# bluetooth_version.net
KiCad netlist of a schematic drawn in EAGLE
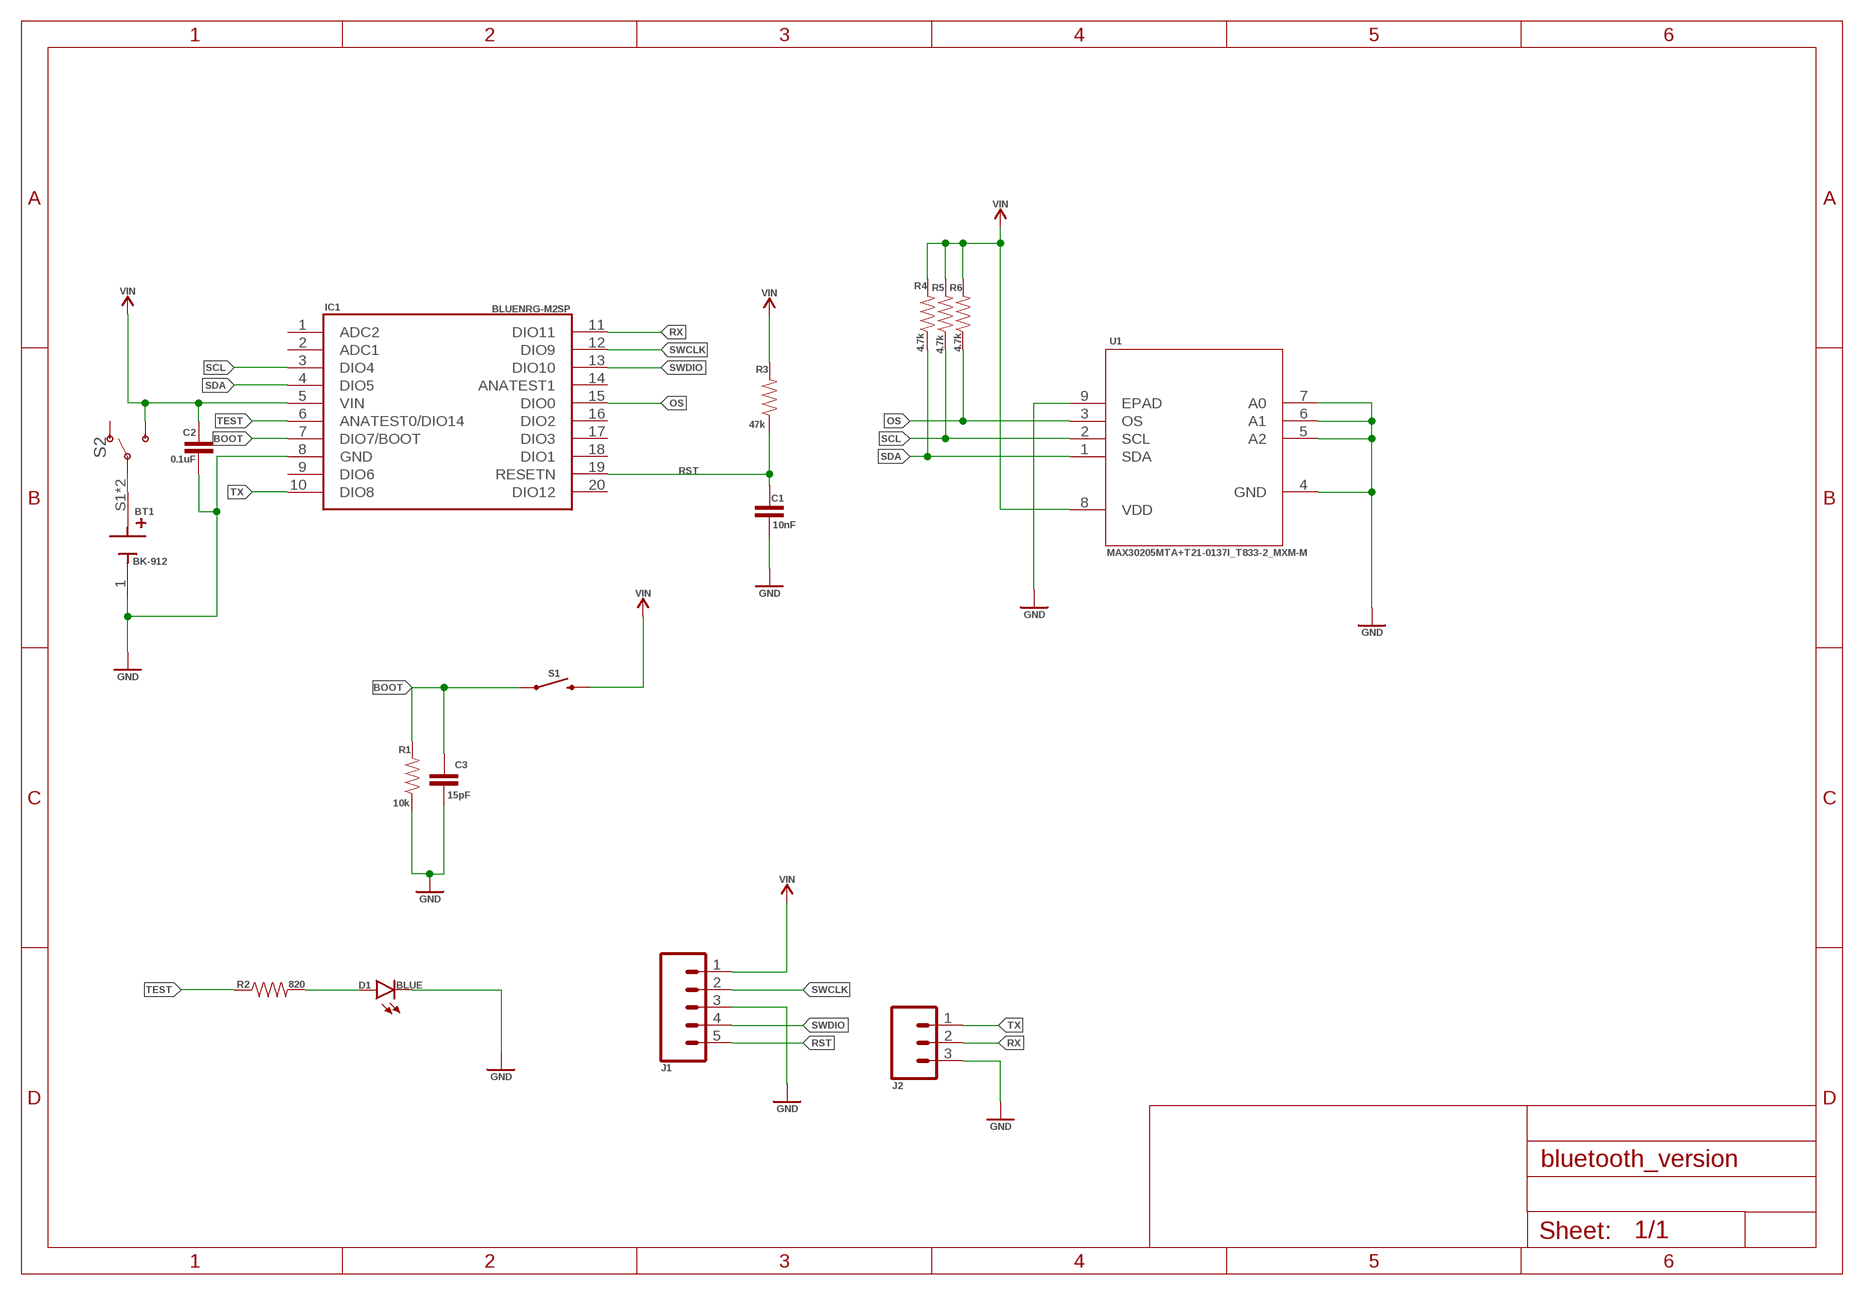
[diagram p0: schematic, sheet 1]

(export (version "E")
  (design (tool "Eeschema 10.0.6"))
  (components
    (comp (ref "BT1")
      (value "BK-912")
      (footprint "eagle-import:BAT_BK-912")
      (fields (field (name "MF") "MPD (Memory"))
      (libsource (lib "eagle-import") (part "BK-912"))
    )
    (comp (ref "C1")
      (value "10nF")
      (footprint "eagle-import:0603")
      (libsource (lib "eagle-import") (part "10NF-0603-50V-10%"))
    )
    (comp (ref "C2")
      (value "0.1uF")
      (footprint "eagle-import:0603")
      (libsource (lib "eagle-import") (part "0.1UF-0603-25V-(+80/-20%)"))
    )
    (comp (ref "C3")
      (value "15pF")
      (footprint "eagle-import:0603")
      (libsource (lib "eagle-import") (part "15PF-0603-50V-5%"))
    )
    (comp (ref "D1")
      (value "BLUE")
      (footprint "eagle-import:LED-0603")
      (libsource (lib "eagle-import") (part "LED-BLUE0603"))
    )
    (comp (ref "IC1")
      (value "BLUENRG-M2SP")
      (footprint "eagle-import:BLUENRGM2SP")
      (fields (field (name "MOUSER_PART_NUMBER") "511-BLUENRG-M2SP"))
      (libsource (lib "eagle-import") (part "BLUENRG-M2SP"))
    )
    (comp (ref "J1")
      (value "CONN_05")
      (footprint "eagle-import:1X05")
      (libsource (lib "eagle-import") (part "CONN_05"))
    )
    (comp (ref "J2")
      (value "455-1750-1-ND")
      (footprint "eagle-import:1X03")
      (libsource (lib "eagle-import") (part "CONN_03"))
    )
    (comp (ref "R1")
      (value "10k")
      (footprint "eagle-import:0603")
      (libsource (lib "eagle-import") (part "10KOHM-0603-1/10W-1%"))
    )
    (comp (ref "R2")
      (value "820")
      (footprint "eagle-import:0603")
      (fields (field (name "SPICEPREFIX") "R"))
      (libsource (lib "eagle-import") (part "8.2KOHM-0603-1/10W-5%"))
    )
    (comp (ref "R3")
      (value "47k")
      (footprint "eagle-import:0603")
      (libsource (lib "eagle-import") (part "47KOHM-0603-1/10W-1%"))
    )
    (comp (ref "R4")
      (value "4.7k")
      (footprint "eagle-import:0603")
      (libsource (lib "eagle-import") (part "4.7KOHM-0603-1/10W-1%"))
    )
    (comp (ref "R5")
      (value "4.7k")
      (footprint "eagle-import:0603")
      (libsource (lib "eagle-import") (part "4.7KOHM-0603-1/10W-1%"))
    )
    (comp (ref "R6")
      (value "4.7k")
      (footprint "eagle-import:0603")
      (libsource (lib "eagle-import") (part "4.7KOHM-0603-1/10W-1%"))
    )
    (comp (ref "S1")
      (value "MOMENTARY-SWITCH-SPST-SMD-4.6X2.8MM")
      (footprint "eagle-import:TACTILE_SWITCH_SMD_4.6X2.8MM")
      (libsource (lib "eagle-import") (part "MOMENTARY-SWITCH-SPST-SMD-4.6X2.8MM"))
    )
    (comp (ref "S2")
      (value "SWITCH-SPDT-SMD-RIGHT-ANGLE")
      (footprint "eagle-import:SWITCH_SPST_SMD_A")
      (libsource (lib "eagle-import") (part "SWITCH-SPDT-SMD-RIGHT-ANGLE"))
    )
    (comp (ref "U1")
      (value "MAX30205MTA+T21-0137I_T833-2_MXM-M")
      (footprint "eagle-import:21-0137I_T833-2_MXM-M")
      (fields
        (field (name "MANUFACTURER_PART_NUMBER") "MAX30205MTA+T")
        (field (name "COPYRIGHT") "Copyright (C) 2018 Accelerated Designs. All rights reserved")
      )
      (libsource (lib "eagle-import") (part "MAX30205MTA+T21-0137I_T833-2_MXM-M"))
    )
  )
  (nets
    (net (code "1") (name "BOOT") (class "Default")
      (node (ref "C3") (pin "1") (pinfunction "1_1") (pintype "passive"))
      (node (ref "IC1") (pin "7") (pinfunction "DIO7/BOOT_7") (pintype "bidirectional"))
      (node (ref "R1") (pin "2") (pinfunction "2_2") (pintype "passive"))
      (node (ref "S1") (pin "1") (pinfunction "1_1") (pintype "passive"))
      (node (ref "S1") (pin "2") (pinfunction "1_2") (pintype "passive"))
    )
    (net (code "2") (name "GND") (class "Default")
      (node (ref "BT1") (pin "1") (pinfunction "-_1") (pintype "passive"))
      (node (ref "C1") (pin "2") (pinfunction "2_2") (pintype "passive"))
      (node (ref "C2") (pin "2") (pinfunction "2_2") (pintype "passive"))
      (node (ref "C3") (pin "2") (pinfunction "2_2") (pintype "passive"))
      (node (ref "D1") (pin "C") (pinfunction "C_C") (pintype "passive"))
      (node (ref "IC1") (pin "8") (pinfunction "GND_8") (pintype "bidirectional"))
      (node (ref "J1") (pin "3") (pinfunction "3_3") (pintype "passive"))
      (node (ref "J2") (pin "3") (pinfunction "3_3") (pintype "passive"))
      (node (ref "R1") (pin "1") (pinfunction "1_1") (pintype "passive"))
      (node (ref "U1") (pin "4") (pinfunction "GND_4") (pintype "passive"))
      (node (ref "U1") (pin "5") (pinfunction "A2_5") (pintype "bidirectional"))
      (node (ref "U1") (pin "6") (pinfunction "A1_6") (pintype "bidirectional"))
      (node (ref "U1") (pin "7") (pinfunction "A0_7") (pintype "bidirectional"))
      (node (ref "U1") (pin "9") (pinfunction "EPAD_9") (pintype "passive"))
    )
    (net (code "3") (name "Net-(D1-PadA)") (class "Default")
      (node (ref "D1") (pin "A") (pinfunction "A_A") (pintype "passive"))
      (node (ref "R2") (pin "2") (pinfunction "2_2") (pintype "passive"))
    )
    (net (code "4") (name "Net-(S2-P)") (class "Default")
      (node (ref "BT1") (pin "S1") (pinfunction "+_S1") (pintype "passive"))
      (node (ref "BT1") (pin "S2") (pinfunction "+_S2") (pintype "passive"))
      (node (ref "S2") (pin "2") (pinfunction "P_2") (pintype "passive"))
    )
    (net (code "5") (name "OS") (class "Default")
      (node (ref "IC1") (pin "15") (pinfunction "DIO0_15") (pintype "bidirectional"))
      (node (ref "R6") (pin "1") (pinfunction "1_1") (pintype "passive"))
      (node (ref "U1") (pin "3") (pinfunction "OS_3") (pintype "passive"))
    )
    (net (code "6") (name "RST") (class "Default")
      (node (ref "C1") (pin "1") (pinfunction "1_1") (pintype "passive"))
      (node (ref "IC1") (pin "19") (pinfunction "RESETN_19") (pintype "bidirectional"))
      (node (ref "J1") (pin "5") (pinfunction "5_5") (pintype "passive"))
      (node (ref "R3") (pin "1") (pinfunction "1_1") (pintype "passive"))
    )
    (net (code "7") (name "RX") (class "Default")
      (node (ref "IC1") (pin "11") (pinfunction "DIO11_11") (pintype "bidirectional"))
      (node (ref "J2") (pin "2") (pinfunction "2_2") (pintype "passive"))
    )
    (net (code "8") (name "SCL") (class "Default")
      (node (ref "IC1") (pin "3") (pinfunction "DIO4_3") (pintype "bidirectional"))
      (node (ref "R5") (pin "1") (pinfunction "1_1") (pintype "passive"))
      (node (ref "U1") (pin "2") (pinfunction "SCL_2") (pintype "passive"))
    )
    (net (code "9") (name "SDA") (class "Default")
      (node (ref "IC1") (pin "4") (pinfunction "DIO5_4") (pintype "bidirectional"))
      (node (ref "R4") (pin "1") (pinfunction "1_1") (pintype "passive"))
      (node (ref "U1") (pin "1") (pinfunction "SDA_1") (pintype "passive"))
    )
    (net (code "10") (name "SWCLK") (class "Default")
      (node (ref "IC1") (pin "12") (pinfunction "DIO9_12") (pintype "bidirectional"))
      (node (ref "J1") (pin "2") (pinfunction "2_2") (pintype "passive"))
    )
    (net (code "11") (name "SWDIO") (class "Default")
      (node (ref "IC1") (pin "13") (pinfunction "DIO10_13") (pintype "bidirectional"))
      (node (ref "J1") (pin "4") (pinfunction "4_4") (pintype "passive"))
    )
    (net (code "12") (name "TEST") (class "Default")
      (node (ref "IC1") (pin "6") (pinfunction "ANATEST0/DIO14_6") (pintype "bidirectional"))
      (node (ref "R2") (pin "1") (pinfunction "1_1") (pintype "passive"))
    )
    (net (code "13") (name "TX") (class "Default")
      (node (ref "IC1") (pin "10") (pinfunction "DIO8_10") (pintype "bidirectional"))
      (node (ref "J2") (pin "1") (pinfunction "1_1") (pintype "passive"))
    )
    (net (code "14") (name "VIN") (class "Default")
      (node (ref "C2") (pin "1") (pinfunction "1_1") (pintype "passive"))
      (node (ref "IC1") (pin "5") (pinfunction "VIN_5") (pintype "bidirectional"))
      (node (ref "J1") (pin "1") (pinfunction "1_1") (pintype "passive"))
      (node (ref "R3") (pin "2") (pinfunction "2_2") (pintype "passive"))
      (node (ref "R4") (pin "2") (pinfunction "2_2") (pintype "passive"))
      (node (ref "R5") (pin "2") (pinfunction "2_2") (pintype "passive"))
      (node (ref "R6") (pin "2") (pinfunction "2_2") (pintype "passive"))
      (node (ref "S1") (pin "3") (pinfunction "2_3") (pintype "passive"))
      (node (ref "S1") (pin "4") (pinfunction "2_4") (pintype "passive"))
      (node (ref "S2") (pin "3") (pinfunction "S_3") (pintype "passive"))
      (node (ref "U1") (pin "8") (pinfunction "VDD_8") (pintype "power_in"))
    )
    (net (code "15") (name "unconnected-(IC1-ADC1-Pad2)") (class "Default")
      (node (ref "IC1") (pin "2") (pinfunction "ADC1_2") (pintype "bidirectional"))
    )
    (net (code "16") (name "unconnected-(IC1-ADC2-Pad1)") (class "Default")
      (node (ref "IC1") (pin "1") (pinfunction "ADC2_1") (pintype "bidirectional"))
    )
    (net (code "17") (name "unconnected-(IC1-ANATEST1-Pad14)") (class "Default")
      (node (ref "IC1") (pin "14") (pinfunction "ANATEST1_14") (pintype "bidirectional"))
    )
    (net (code "18") (name "unconnected-(IC1-DIO1-Pad18)") (class "Default")
      (node (ref "IC1") (pin "18") (pinfunction "DIO1_18") (pintype "bidirectional"))
    )
    (net (code "19") (name "unconnected-(IC1-DIO2-Pad16)") (class "Default")
      (node (ref "IC1") (pin "16") (pinfunction "DIO2_16") (pintype "bidirectional"))
    )
    (net (code "20") (name "unconnected-(IC1-DIO3-Pad17)") (class "Default")
      (node (ref "IC1") (pin "17") (pinfunction "DIO3_17") (pintype "bidirectional"))
    )
    (net (code "21") (name "unconnected-(IC1-DIO6-Pad9)") (class "Default")
      (node (ref "IC1") (pin "9") (pinfunction "DIO6_9") (pintype "bidirectional"))
    )
    (net (code "22") (name "unconnected-(IC1-DIO12-Pad20)") (class "Default")
      (node (ref "IC1") (pin "20") (pinfunction "DIO12_20") (pintype "bidirectional"))
    )
    (net (code "23") (name "unconnected-(S2-O-Pad1)") (class "Default")
      (node (ref "S2") (pin "1") (pinfunction "O_1") (pintype "passive"))
    )
  )
)
